# Digital.net
KiCad netlist of a schematic drawn in Altium Designer
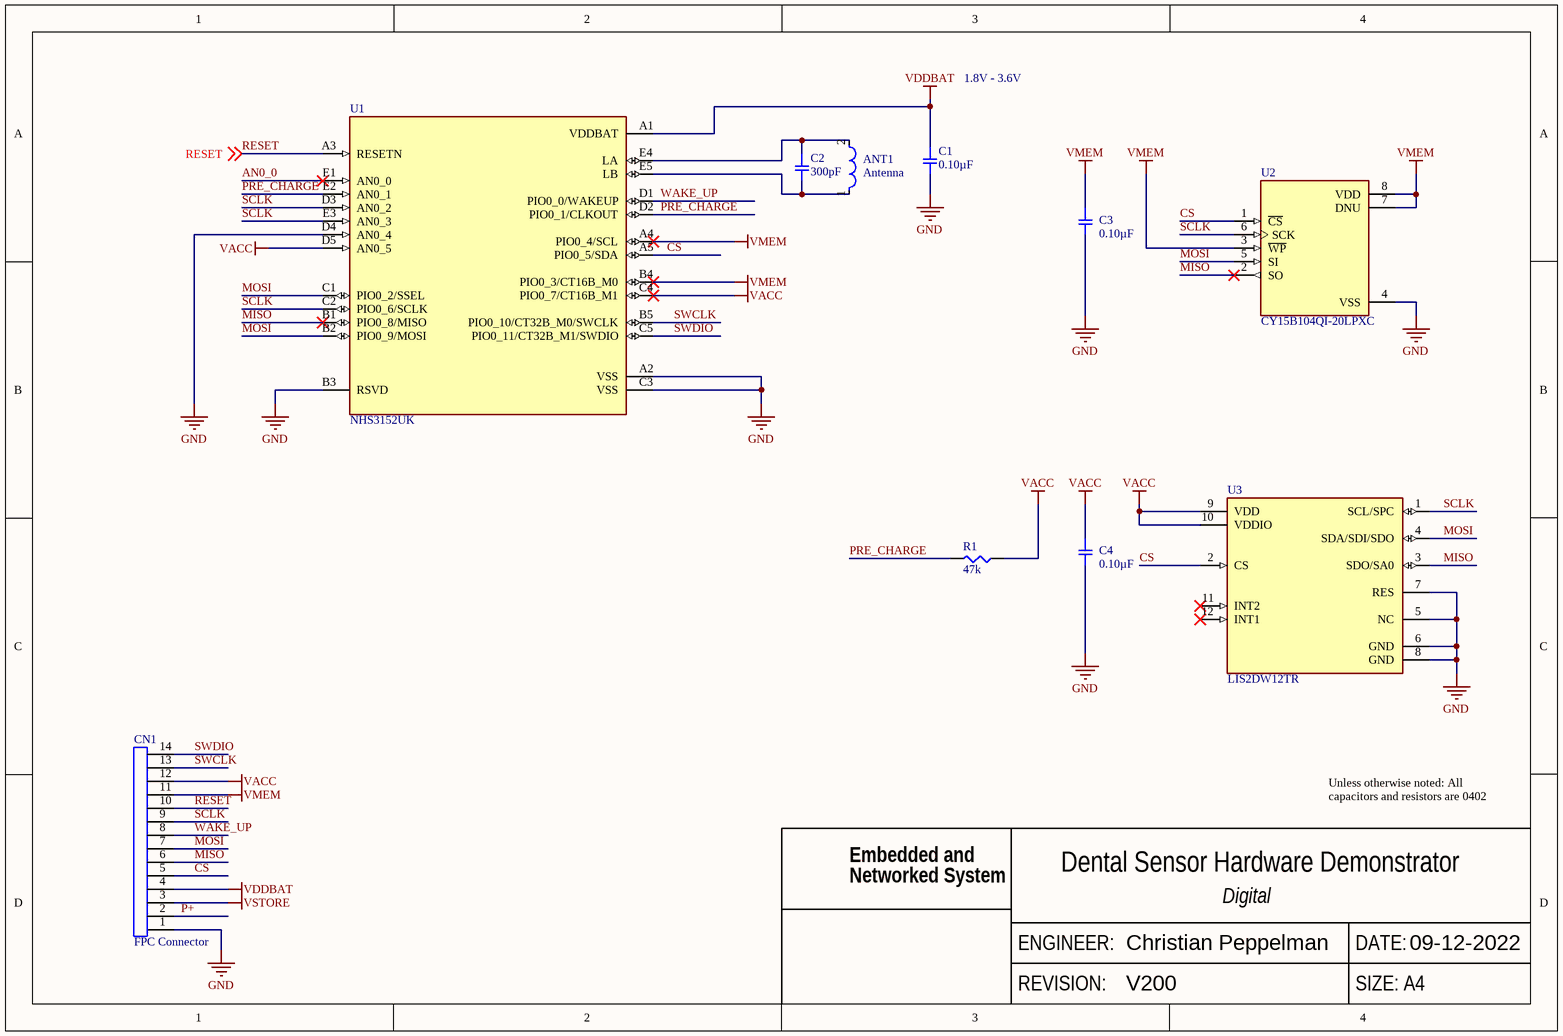
[diagram p0: Digital.SchDoc]

(export (version "E")
  (design (tool "Eeschema 10.0.6"))
  (components
    (comp (ref "ANT1")
      (value "Antenna")
      (footprint "NFC Antenna")
      (description "Track 0.2; Gap 0.1; Height 4.6; Width 14.5;")
      (libsource (lib "Library") (part "NFC Antenna"))
    )
    (comp (ref "C1")
      (value "0.10µF")
      (footprint "RESC1005X03N")
      (description "CAP CER 0.1UF 6.3V X5R 0402")
      (fields
        (field (name "DIGI-KEY PART NUMBER") "490-6287-1-ND")
        (field (name "PART NUMBER") "GRM155R60J104KA01D")
      )
      (libsource (lib "capacitor_murata_0402") (part "GRM155R60J104KA01D"))
    )
    (comp (ref "C2")
      (value "300pF")
      (footprint "RESC1005X03N")
      (description "CAP CER 300PF 50V NP0 0402")
      (fields
        (field (name "DIGI-KEY PART NUMBER") "490-3234-1-ND")
        (field (name "PART NUMBER") "GRM1555C1H301JA01D")
      )
      (libsource (lib "capacitor_murata_0402") (part "GRM1555C1H301JA01D"))
    )
    (comp (ref "C3")
      (value "0.10µF")
      (footprint "RESC1005X03N")
      (description "CAP CER 0.1UF 6.3V X5R 0402")
      (fields
        (field (name "DIGI-KEY PART NUMBER") "490-6287-1-ND")
        (field (name "PART NUMBER") "GRM155R60J104KA01D")
      )
      (libsource (lib "capacitor_murata_0402") (part "GRM155R60J104KA01D"))
    )
    (comp (ref "C4")
      (value "0.10µF")
      (footprint "RESC1005X03N")
      (description "CAP CER 0.1UF 6.3V X5R 0402")
      (fields
        (field (name "DIGI-KEY PART NUMBER") "490-6287-1-ND")
        (field (name "PART NUMBER") "GRM155R60J104KA01D")
      )
      (libsource (lib "capacitor_murata_0402") (part "GRM155R60J104KA01D"))
    )
    (comp (ref "CN1")
      (value "FPC Connector")
      (footprint "52745-1497")
      (description "FFC / FPC Board Connector, 0.5 mm, 14 Contacts, Receptacle, Easy-On 52745, Surface Mount, Top")
      (libsource (lib "Library") (part "52745-1497"))
    )
    (comp (ref "R1")
      (value "47k")
      (footprint "CAPC1005X03N")
      (description "RES SMD 47K OHM 1% 1/10W 0402")
      (fields
        (field (name "PART NUMBER") "ERJ-2RKF4702X")
        (field (name "DIGI-KEY PART NUMBER") "P47.0KLCT-ND")
      )
      (libsource (lib "Panasonic_ERJ_0402") (part "ERJ-2RKF4702X"))
    )
    (comp (ref "U1")
      (value "NHS3152UK")
      (footprint "WLCSP25")
      (description "ARM-microcontrollers - MCU NTAG NHS3152 NFC")
      (libsource (lib "Library") (part "NHS3152UK"))
    )
    (comp (ref "U2")
      (value "CY15B104QI-20LPXC")
      (footprint "8-GQFN")
      (description "FRAM (Ferroelectric RAM) Memory IC 4Mbit SPI 20 MHz 8-GQFN (3.23x3.28)")
      (libsource (lib "Library") (part "CY15B104QI-20LPXC"))
    )
    (comp (ref "U3")
      (value "LIS2DW12TR")
      (footprint "FP-LGA12-DM00170568-MFG")
      (description "ACCEL 2-16G I2C/SPI 12LGA")
      (fields
        (field (name "OCTOPART") "https://octopart.com/lis2dw12tr-stmicroelectronics-77080925")
        (field (name "MANUFACTURER") "STMicroelectronics")
      )
      (libsource (lib "Altium Content Vault") (part "8197bdef8f004bf043f7592a5d62978"))
    )
  )
  (nets
    (net (code "1") (name "/AN0_0") (class "Default")
      (node (ref "U1") (pin "E1") (pinfunction "AN0_0_E1") (pintype "input+no_connect"))
    )
    (net (code "2") (name "/CS") (class "Default")
      (node (ref "CN1") (pin "5") (pintype "passive"))
      (node (ref "U1") (pin "A5") (pinfunction "PIO0_5/SDA_A5") (pintype "bidirectional"))
      (node (ref "U2") (pin "1") (pinfunction "~{CS}_1") (pintype "input"))
      (node (ref "U3") (pin "2") (pinfunction "CS_2") (pintype "input"))
    )
    (net (code "3") (name "/MISO") (class "Default")
      (node (ref "CN1") (pin "6") (pintype "passive"))
      (node (ref "U1") (pin "B1") (pinfunction "PIO0_8/MISO_B1") (pintype "bidirectional"))
      (node (ref "U2") (pin "2") (pinfunction "SO_2") (pintype "output"))
      (node (ref "U3") (pin "3") (pinfunction "SDO/SA0_3") (pintype "bidirectional"))
    )
    (net (code "4") (name "/MOSI") (class "Default")
      (node (ref "CN1") (pin "7") (pintype "passive"))
      (node (ref "U1") (pin "B2") (pinfunction "PIO0_9/MOSI_B2") (pintype "bidirectional"))
      (node (ref "U1") (pin "C1") (pinfunction "PIO0_2/SSEL_C1") (pintype "bidirectional"))
      (node (ref "U2") (pin "5") (pinfunction "SI_5") (pintype "input"))
      (node (ref "U3") (pin "4") (pinfunction "SDA/SDI/SDO_4") (pintype "bidirectional"))
    )
    (net (code "5") (name "/P+") (class "Default") (node (ref "CN1") (pin "2") (pintype "passive")))
    (net (code "6") (name "/PRE_CHARGE") (class "Default")
      (node (ref "R1") (pin "2") (pinfunction "2_2") (pintype "passive"))
      (node (ref "U1") (pin "D2") (pinfunction "PIO0_1/CLKOUT_D2") (pintype "bidirectional"))
      (node (ref "U1") (pin "E2") (pinfunction "AN0_1_E2") (pintype "input"))
    )
    (net (code "7") (name "/SCLK") (class "Default")
      (node (ref "CN1") (pin "9") (pintype "passive"))
      (node (ref "U1") (pin "C2") (pinfunction "PIO0_6/SCLK_C2") (pintype "bidirectional"))
      (node (ref "U1") (pin "D3") (pinfunction "AN0_2_D3") (pintype "input"))
      (node (ref "U1") (pin "E3") (pinfunction "AN0_3_E3") (pintype "input"))
      (node (ref "U2") (pin "6") (pinfunction "SCK_6") (pintype "input"))
      (node (ref "U3") (pin "1") (pinfunction "SCL/SPC_1") (pintype "bidirectional"))
    )
    (net (code "8") (name "/SWCLK") (class "Default")
      (node (ref "CN1") (pin "13") (pintype "passive"))
      (node (ref "U1") (pin "B5") (pinfunction "PIO0_10/CT32B_M0/SWCLK_B5") (pintype "bidirectional"))
    )
    (net (code "9") (name "/SWDIO") (class "Default")
      (node (ref "CN1") (pin "14") (pintype "passive"))
      (node (ref "U1") (pin "C5") (pinfunction "PIO0_11/CT32B_M1/SWDIO_C5") (pintype "bidirectional"))
    )
    (net (code "10") (name "/WAKE_UP") (class "Default")
      (node (ref "CN1") (pin "8") (pintype "passive"))
      (node (ref "U1") (pin "D1") (pinfunction "PIO0_0/WAKEUP_D1") (pintype "bidirectional"))
    )
    (net (code "11") (name "GND") (class "Default")
      (node (ref "C1") (pin "2") (pinfunction "2_2") (pintype "passive"))
      (node (ref "C3") (pin "2") (pinfunction "2_2") (pintype "passive"))
      (node (ref "C4") (pin "2") (pinfunction "2_2") (pintype "passive"))
      (node (ref "CN1") (pin "1") (pintype "passive"))
      (node (ref "U1") (pin "A2") (pinfunction "VSS_A2") (pintype "power_in"))
      (node (ref "U1") (pin "B3") (pinfunction "RSVD_B3") (pintype "passive"))
      (node (ref "U1") (pin "C3") (pinfunction "VSS_C3") (pintype "power_in"))
      (node (ref "U1") (pin "D4") (pinfunction "AN0_4_D4") (pintype "input"))
      (node (ref "U2") (pin "4") (pinfunction "VSS_4") (pintype "power_in"))
      (node (ref "U3") (pin "5") (pinfunction "NC_5") (pintype "passive"))
      (node (ref "U3") (pin "6") (pinfunction "GND_6") (pintype "power_in"))
      (node (ref "U3") (pin "7") (pinfunction "RES_7") (pintype "passive"))
      (node (ref "U3") (pin "8") (pinfunction "GND_8") (pintype "power_in"))
    )
    (net (code "12") (name "Net-(U1-LA)") (class "Default")
      (node (ref "ANT1") (pin "2") (pinfunction "2_2") (pintype "passive"))
      (node (ref "C2") (pin "1") (pinfunction "1_1") (pintype "passive"))
      (node (ref "U1") (pin "E4") (pinfunction "LA_E4") (pintype "bidirectional"))
    )
    (net (code "13") (name "Net-(U1-LB)") (class "Default")
      (node (ref "ANT1") (pin "1") (pinfunction "1_1") (pintype "passive"))
      (node (ref "C2") (pin "2") (pinfunction "2_2") (pintype "passive"))
      (node (ref "U1") (pin "E5") (pinfunction "LB_E5") (pintype "bidirectional"))
    )
    (net (code "14") (name "RESET") (class "Default")
      (node (ref "CN1") (pin "10") (pintype "passive"))
      (node (ref "U1") (pin "A3") (pinfunction "RESETN_A3") (pintype "input"))
    )
    (net (code "15") (name "VACC") (class "Default")
      (node (ref "C4") (pin "1") (pinfunction "1_1") (pintype "passive"))
      (node (ref "CN1") (pin "12") (pintype "passive"))
      (node (ref "R1") (pin "1") (pinfunction "1_1") (pintype "passive"))
      (node (ref "U1") (pin "C4") (pinfunction "PIO0_7/CT16B_M1_C4") (pintype "bidirectional"))
      (node (ref "U1") (pin "D5") (pinfunction "AN0_5_D5") (pintype "input"))
      (node (ref "U3") (pin "10") (pinfunction "VDDIO_10") (pintype "power_in"))
      (node (ref "U3") (pin "9") (pinfunction "VDD_9") (pintype "power_in"))
    )
    (net (code "16") (name "VDDBAT") (class "Default")
      (node (ref "C1") (pin "1") (pinfunction "1_1") (pintype "passive"))
      (node (ref "CN1") (pin "4") (pintype "passive"))
      (node (ref "U1") (pin "A1") (pinfunction "VDDBAT_A1") (pintype "power_in"))
    )
    (net (code "17") (name "VMEM") (class "Default")
      (node (ref "C3") (pin "1") (pinfunction "1_1") (pintype "passive"))
      (node (ref "CN1") (pin "11") (pintype "passive"))
      (node (ref "U1") (pin "A4") (pinfunction "PIO0_4/SCL_A4") (pintype "bidirectional"))
      (node (ref "U1") (pin "B4") (pinfunction "PIO0_3/CT16B_M0_B4") (pintype "bidirectional"))
      (node (ref "U2") (pin "3") (pinfunction "~{WP}_3") (pintype "input"))
      (node (ref "U2") (pin "7") (pinfunction "DNU_7") (pintype "passive"))
      (node (ref "U2") (pin "8") (pinfunction "VDD_8") (pintype "power_in"))
    )
    (net (code "18") (name "VSTORE") (class "Default") (node (ref "CN1") (pin "3") (pintype "passive")))
    (net (code "19") (name "unconnected-(U3-INT1-Pad12)") (class "Default")
      (node (ref "U3") (pin "12") (pinfunction "INT1_12") (pintype "input+no_connect"))
    )
    (net (code "20") (name "unconnected-(U3-INT2-Pad11)") (class "Default")
      (node (ref "U3") (pin "11") (pinfunction "INT2_11") (pintype "input+no_connect"))
    )
  )
)
